# core.net
KiCad netlist of a schematic drawn in Altium Designer
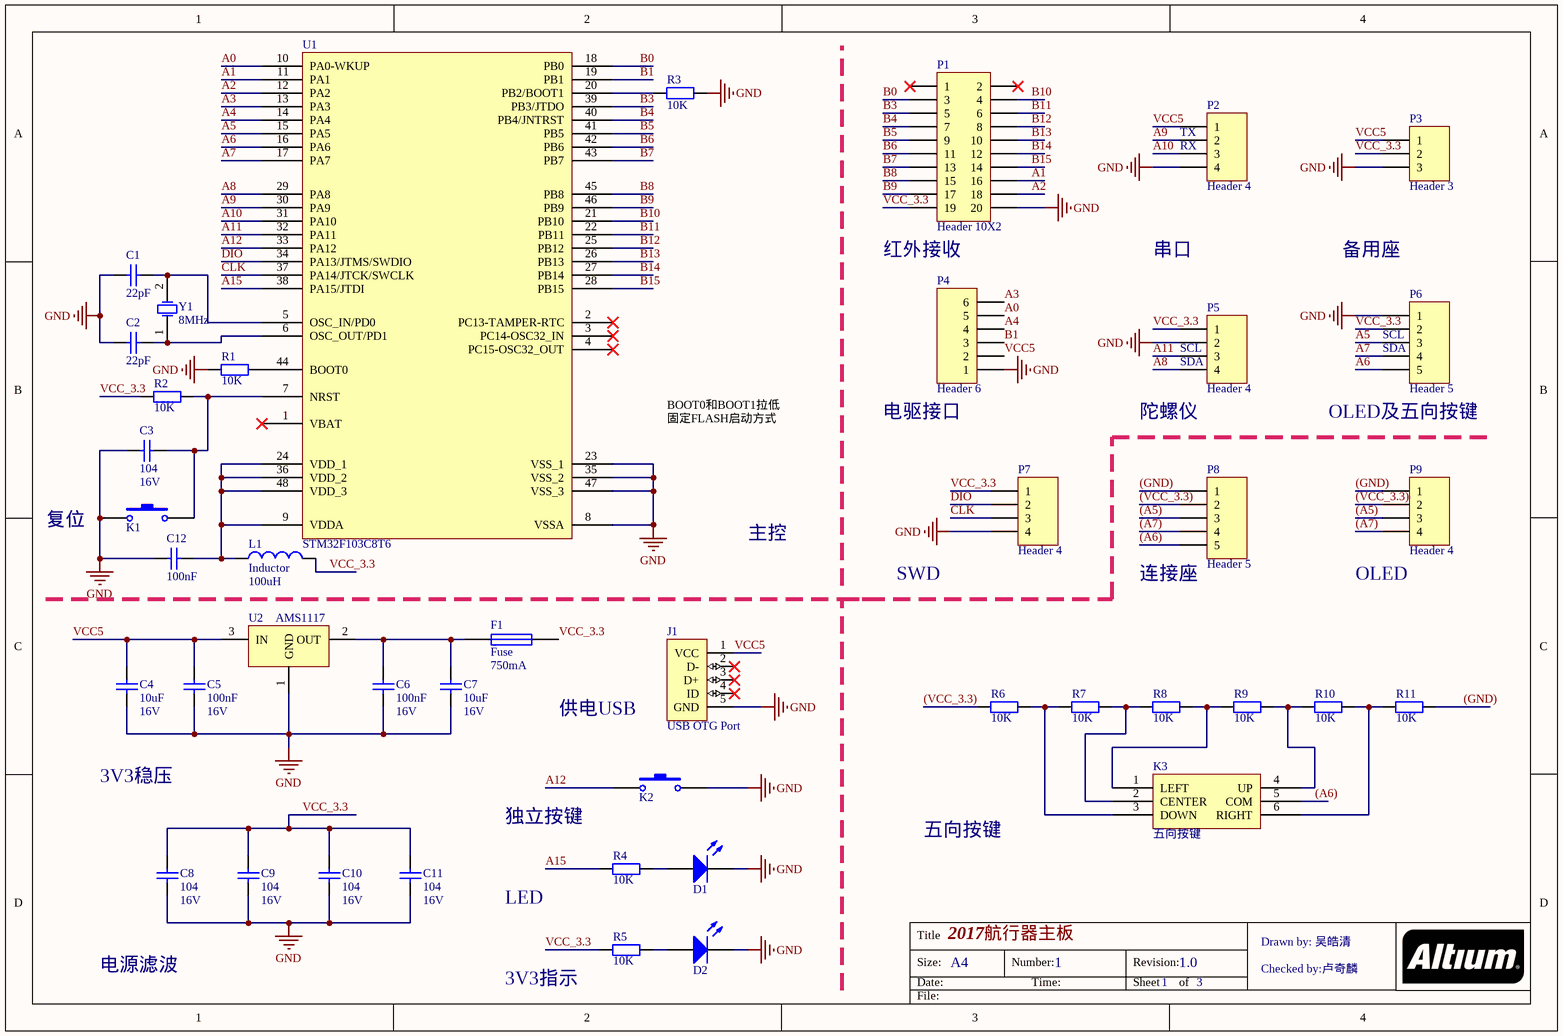
[diagram p0: core.SchDoc]

(export (version "E")
  (design (tool "Eeschema 10.0.6"))
  (components
    (comp (ref "C1")
      (value "22pF")
      (footprint "0805")
      (fields
        (field (name "Comment") "Cap")
        (field (name "原理图绘制者") "刘永钦")
        (field (name "原理图提供者") "刘永钦")
        (field (name "原理图审核人1") "徐鹏飞")
        (field (name "封装0805绘制者") "刘永钦")
        (field (name "封装0805提供者") "刘永钦")
        (field (name "封装0805审核人1") "徐鹏飞")
        (field (name "原理图审核人2") "朱觉文")
        (field (name "封装0805审核人2") "朱觉文")
        (field (name "封装0603绘制者") "刘永钦")
        (field (name "封装0603提供者") "刘永钦")
        (field (name "封装0603审核人1") "朱觉文")
        (field (name "封装0603审核人2") "徐鹏飞")
      )
      (libsource (lib "自动化研究所集成库20170403") (part "Cap"))
    )
    (comp (ref "C2")
      (value "22pF")
      (footprint "0805")
      (fields
        (field (name "Comment") "Cap")
        (field (name "原理图绘制者") "刘永钦")
        (field (name "原理图提供者") "刘永钦")
        (field (name "原理图审核人1") "徐鹏飞")
        (field (name "封装0805绘制者") "刘永钦")
        (field (name "封装0805提供者") "刘永钦")
        (field (name "封装0805审核人1") "徐鹏飞")
        (field (name "原理图审核人2") "朱觉文")
        (field (name "封装0805审核人2") "朱觉文")
        (field (name "封装0603绘制者") "刘永钦")
        (field (name "封装0603提供者") "刘永钦")
        (field (name "封装0603审核人1") "朱觉文")
        (field (name "封装0603审核人2") "徐鹏飞")
      )
      (libsource (lib "自动化研究所集成库20170403") (part "Cap"))
    )
    (comp (ref "C3")
      (value "104")
      (footprint "0805")
      (fields
        (field (name "PRESSURE VOLTAGE") "16V")
        (field (name "Comment") "Cap")
        (field (name "原理图绘制者") "刘永钦")
        (field (name "原理图提供者") "刘永钦")
        (field (name "原理图审核人1") "徐鹏飞")
        (field (name "封装0805绘制者") "刘永钦")
        (field (name "封装0805提供者") "刘永钦")
        (field (name "封装0805审核人1") "徐鹏飞")
        (field (name "原理图审核人2") "朱觉文")
        (field (name "封装0805审核人2") "朱觉文")
        (field (name "封装0603绘制者") "刘永钦")
        (field (name "封装0603提供者") "刘永钦")
        (field (name "封装0603审核人1") "朱觉文")
        (field (name "封装0603审核人2") "徐鹏飞")
      )
      (libsource (lib "自动化研究所集成库20170403") (part "Cap"))
    )
    (comp (ref "C4")
      (value "10uF")
      (footprint "0805")
      (fields
        (field (name "PRESSURE VOLTAGE") "16V")
        (field (name "Comment") "Cap")
        (field (name "原理图绘制者") "刘永钦")
        (field (name "原理图提供者") "刘永钦")
        (field (name "原理图审核人1") "徐鹏飞")
        (field (name "封装0805绘制者") "刘永钦")
        (field (name "封装0805提供者") "刘永钦")
        (field (name "封装0805审核人1") "徐鹏飞")
        (field (name "原理图审核人2") "朱觉文")
        (field (name "封装0805审核人2") "朱觉文")
        (field (name "封装0603绘制者") "刘永钦")
        (field (name "封装0603提供者") "刘永钦")
        (field (name "封装0603审核人1") "朱觉文")
        (field (name "封装0603审核人2") "徐鹏飞")
      )
      (libsource (lib "自动化研究所集成库20170403") (part "Cap"))
    )
    (comp (ref "C5")
      (value "100nF")
      (footprint "0805")
      (fields
        (field (name "PRESSURE VOLTAGE") "16V")
        (field (name "Comment") "Cap")
        (field (name "原理图绘制者") "刘永钦")
        (field (name "原理图提供者") "刘永钦")
        (field (name "原理图审核人1") "徐鹏飞")
        (field (name "封装0805绘制者") "刘永钦")
        (field (name "封装0805提供者") "刘永钦")
        (field (name "封装0805审核人1") "徐鹏飞")
        (field (name "原理图审核人2") "朱觉文")
        (field (name "封装0805审核人2") "朱觉文")
        (field (name "封装0603绘制者") "刘永钦")
        (field (name "封装0603提供者") "刘永钦")
        (field (name "封装0603审核人1") "朱觉文")
        (field (name "封装0603审核人2") "徐鹏飞")
      )
      (libsource (lib "自动化研究所集成库20170403") (part "Cap"))
    )
    (comp (ref "C6")
      (value "100nF")
      (footprint "0805")
      (fields
        (field (name "PRESSURE VOLTAGE") "16V")
        (field (name "Comment") "Cap")
        (field (name "原理图绘制者") "刘永钦")
        (field (name "原理图提供者") "刘永钦")
        (field (name "原理图审核人1") "徐鹏飞")
        (field (name "封装0805绘制者") "刘永钦")
        (field (name "封装0805提供者") "刘永钦")
        (field (name "封装0805审核人1") "徐鹏飞")
        (field (name "原理图审核人2") "朱觉文")
        (field (name "封装0805审核人2") "朱觉文")
        (field (name "封装0603绘制者") "刘永钦")
        (field (name "封装0603提供者") "刘永钦")
        (field (name "封装0603审核人1") "朱觉文")
        (field (name "封装0603审核人2") "徐鹏飞")
      )
      (libsource (lib "自动化研究所集成库20170403") (part "Cap"))
    )
    (comp (ref "C7")
      (value "10uF")
      (footprint "0805")
      (fields
        (field (name "PRESSURE VOLTAGE") "16V")
        (field (name "Comment") "Cap")
        (field (name "原理图绘制者") "刘永钦")
        (field (name "原理图提供者") "刘永钦")
        (field (name "原理图审核人1") "徐鹏飞")
        (field (name "封装0805绘制者") "刘永钦")
        (field (name "封装0805提供者") "刘永钦")
        (field (name "封装0805审核人1") "徐鹏飞")
        (field (name "原理图审核人2") "朱觉文")
        (field (name "封装0805审核人2") "朱觉文")
        (field (name "封装0603绘制者") "刘永钦")
        (field (name "封装0603提供者") "刘永钦")
        (field (name "封装0603审核人1") "朱觉文")
        (field (name "封装0603审核人2") "徐鹏飞")
      )
      (libsource (lib "自动化研究所集成库20170403") (part "Cap"))
    )
    (comp (ref "C8")
      (value "104")
      (footprint "0805")
      (fields
        (field (name "PRESSURE VOLTAGE") "16V")
        (field (name "Comment") "Cap")
        (field (name "原理图绘制者") "刘永钦")
        (field (name "原理图提供者") "刘永钦")
        (field (name "原理图审核人1") "徐鹏飞")
        (field (name "封装0805绘制者") "刘永钦")
        (field (name "封装0805提供者") "刘永钦")
        (field (name "封装0805审核人1") "徐鹏飞")
        (field (name "原理图审核人2") "朱觉文")
        (field (name "封装0805审核人2") "朱觉文")
        (field (name "封装0603绘制者") "刘永钦")
        (field (name "封装0603提供者") "刘永钦")
        (field (name "封装0603审核人1") "朱觉文")
        (field (name "封装0603审核人2") "徐鹏飞")
      )
      (libsource (lib "自动化研究所集成库20170403") (part "Cap"))
    )
    (comp (ref "C9")
      (value "104")
      (footprint "0805")
      (fields
        (field (name "PRESSURE VOLTAGE") "16V")
        (field (name "Comment") "Cap")
        (field (name "原理图绘制者") "刘永钦")
        (field (name "原理图提供者") "刘永钦")
        (field (name "原理图审核人1") "徐鹏飞")
        (field (name "封装0805绘制者") "刘永钦")
        (field (name "封装0805提供者") "刘永钦")
        (field (name "封装0805审核人1") "徐鹏飞")
        (field (name "原理图审核人2") "朱觉文")
        (field (name "封装0805审核人2") "朱觉文")
        (field (name "封装0603绘制者") "刘永钦")
        (field (name "封装0603提供者") "刘永钦")
        (field (name "封装0603审核人1") "朱觉文")
        (field (name "封装0603审核人2") "徐鹏飞")
      )
      (libsource (lib "自动化研究所集成库20170403") (part "Cap"))
    )
    (comp (ref "C10")
      (value "104")
      (footprint "0805")
      (fields
        (field (name "PRESSURE VOLTAGE") "16V")
        (field (name "Comment") "Cap")
        (field (name "原理图绘制者") "刘永钦")
        (field (name "原理图提供者") "刘永钦")
        (field (name "原理图审核人1") "徐鹏飞")
        (field (name "封装0805绘制者") "刘永钦")
        (field (name "封装0805提供者") "刘永钦")
        (field (name "封装0805审核人1") "徐鹏飞")
        (field (name "原理图审核人2") "朱觉文")
        (field (name "封装0805审核人2") "朱觉文")
        (field (name "封装0603绘制者") "刘永钦")
        (field (name "封装0603提供者") "刘永钦")
        (field (name "封装0603审核人1") "朱觉文")
        (field (name "封装0603审核人2") "徐鹏飞")
      )
      (libsource (lib "自动化研究所集成库20170403") (part "Cap"))
    )
    (comp (ref "C11")
      (value "104")
      (footprint "0805")
      (fields
        (field (name "PRESSURE VOLTAGE") "16V")
        (field (name "Comment") "Cap")
        (field (name "原理图绘制者") "刘永钦")
        (field (name "原理图提供者") "刘永钦")
        (field (name "原理图审核人1") "徐鹏飞")
        (field (name "封装0805绘制者") "刘永钦")
        (field (name "封装0805提供者") "刘永钦")
        (field (name "封装0805审核人1") "徐鹏飞")
        (field (name "原理图审核人2") "朱觉文")
        (field (name "封装0805审核人2") "朱觉文")
        (field (name "封装0603绘制者") "刘永钦")
        (field (name "封装0603提供者") "刘永钦")
        (field (name "封装0603审核人1") "朱觉文")
        (field (name "封装0603审核人2") "徐鹏飞")
      )
      (libsource (lib "自动化研究所集成库20170403") (part "Cap"))
    )
    (comp (ref "C12")
      (value "100nF")
      (footprint "0805")
      (fields
        (field (name "Comment") "Cap")
        (field (name "原理图绘制者") "刘永钦")
        (field (name "原理图提供者") "刘永钦")
        (field (name "原理图审核人1") "徐鹏飞")
        (field (name "封装0805绘制者") "刘永钦")
        (field (name "封装0805提供者") "刘永钦")
        (field (name "封装0805审核人1") "徐鹏飞")
        (field (name "原理图审核人2") "朱觉文")
        (field (name "封装0805审核人2") "朱觉文")
        (field (name "封装0603绘制者") "刘永钦")
        (field (name "封装0603提供者") "刘永钦")
        (field (name "封装0603审核人1") "朱觉文")
        (field (name "封装0603审核人2") "徐鹏飞")
      )
      (libsource (lib "自动化研究所集成库20170403") (part "Cap"))
    )
    (comp (ref "D1")
      (value "LED")
      (footprint "LED_0805")
      (fields
        (field (name "原理图绘制者") "刘永钦")
        (field (name "原理图提供者") "刘永钦")
        (field (name "原理图审核人1") "徐鹏飞")
        (field (name "封装1210LED绘制者") "刘永钦")
        (field (name "封装1210LED提供者") "刘永钦")
        (field (name "封装1210LED审核人1") "徐鹏飞")
        (field (name "封装LED_3MM绘制者") "刘永钦")
        (field (name "封装LED_3MM提供者") "刘永钦")
        (field (name "封装LED_0805绘制者") "刘永钦")
        (field (name "封装LED_0805提供者") "刘永钦")
        (field (name "封装LED_0805审核人1") "徐鹏飞")
        (field (name "原理图审核人2") "朱觉文")
        (field (name "封装1210LED审核人2") "朱觉文")
        (field (name "封装LED_0805审核人2") "朱觉文")
        (field (name "封装LED_3MM审核者2") "朱觉文")
        (field (name "封装LED0603绘制者") "刘永钦")
        (field (name "封装LED0603审核人2") "朱觉文")
        (field (name "封装LED0603提供者") "刘永钦")
        (field (name "封装LED0603审核人1") "徐鹏飞")
      )
      (libsource (lib "自动化研究所集成库20170403") (part "LED"))
    )
    (comp (ref "D2")
      (value "LED")
      (footprint "LED_0805")
      (fields
        (field (name "原理图绘制者") "刘永钦")
        (field (name "原理图提供者") "刘永钦")
        (field (name "原理图审核人1") "徐鹏飞")
        (field (name "封装1210LED绘制者") "刘永钦")
        (field (name "封装1210LED提供者") "刘永钦")
        (field (name "封装1210LED审核人1") "徐鹏飞")
        (field (name "封装LED_3MM绘制者") "刘永钦")
        (field (name "封装LED_3MM提供者") "刘永钦")
        (field (name "封装LED_0805绘制者") "刘永钦")
        (field (name "封装LED_0805提供者") "刘永钦")
        (field (name "封装LED_0805审核人1") "徐鹏飞")
        (field (name "原理图审核人2") "朱觉文")
        (field (name "封装1210LED审核人2") "朱觉文")
        (field (name "封装LED_0805审核人2") "朱觉文")
        (field (name "封装LED_3MM审核者2") "朱觉文")
        (field (name "封装LED0603绘制者") "刘永钦")
        (field (name "封装LED0603审核人2") "朱觉文")
        (field (name "封装LED0603提供者") "刘永钦")
        (field (name "封装LED0603审核人1") "徐鹏飞")
      )
      (libsource (lib "自动化研究所集成库20170403") (part "LED"))
    )
    (comp (ref "F1")
      (value "Fuse")
      (footprint "0805")
      (fields
        (field (name "I HOLD") "750mA")
        (field (name "封装1812审核人2") "朱觉文")
        (field (name "封装1812审核人1") "徐鹏飞")
        (field (name "封装1812提供者") "刘永钦")
        (field (name "封装1812绘制者") "刘永钦")
        (field (name "原理图审核人2") "朱觉文")
        (field (name "原理图审核人1") "徐鹏飞")
        (field (name "原理图提供者") "刘永钦")
        (field (name "原理图绘制者") "刘永钦")
      )
      (libsource (lib "自动化研究所集成库20170403") (part "Fuse"))
    )
    (comp (ref "J1")
      (value "USB OTG Port")
      (footprint "Micro USB母座贴片")
      (fields
        (field (name "原理图绘制者") "刘永钦")
        (field (name "原理图提供者") "刘永钦")
        (field (name "原理图审核人1") "徐鹏飞")
        (field (name "封装MICRO USB母座贴片绘制者") "刘永钦")
        (field (name "封装MICRO USB母座贴片提供者") "刘永钦")
        (field (name "封装MICRO USB母座贴片审核人1") "徐鹏飞")
        (field (name "原理图审核人2") "朱觉文")
        (field (name "封装MICRO USB母座贴片审核人2") "朱觉文")
      )
      (libsource (lib "自动化研究所集成库20170403") (part "USB OTG Port"))
    )
    (comp (ref "K1")
      (value "Key")
      (footprint "贴片按键3*6mm")
      (fields
        (field (name "原理图绘制者") "刘永钦")
        (field (name "原理图提供者") "刘永钦")
        (field (name "原理图审核人1") "徐鹏飞")
        (field (name "封装贴片按键3*6MM绘制者") "刘永钦")
        (field (name "封装贴片按键3*6MM提供者") "刘永钦")
        (field (name "封装贴片按键3*6MM审核人1") "徐鹏飞")
        (field (name "封装四脚按键6*6MM绘制者") "刘永钦")
        (field (name "封装四脚按键6*6MM提供者") "刘永钦")
        (field (name "封装四脚按键6*6MM审核人1") "徐鹏飞")
        (field (name "原理图审核人2") "朱觉文")
        (field (name "封装四脚按键6*6MM审核人2") "朱觉文")
        (field (name "封装贴片按键3*6MM审核人2") "朱觉文")
      )
      (libsource (lib "自动化研究所集成库20170403") (part "Key"))
    )
    (comp (ref "K2")
      (value "Key")
      (footprint "贴片按键3*6mm")
      (fields
        (field (name "原理图绘制者") "刘永钦")
        (field (name "原理图提供者") "刘永钦")
        (field (name "原理图审核人1") "徐鹏飞")
        (field (name "封装贴片按键3*6MM绘制者") "刘永钦")
        (field (name "封装贴片按键3*6MM提供者") "刘永钦")
        (field (name "封装贴片按键3*6MM审核人1") "徐鹏飞")
        (field (name "封装四脚按键6*6MM绘制者") "刘永钦")
        (field (name "封装四脚按键6*6MM提供者") "刘永钦")
        (field (name "封装四脚按键6*6MM审核人1") "徐鹏飞")
        (field (name "原理图审核人2") "朱觉文")
        (field (name "封装四脚按键6*6MM审核人2") "朱觉文")
        (field (name "封装贴片按键3*6MM审核人2") "朱觉文")
      )
      (libsource (lib "自动化研究所集成库20170403") (part "Key"))
    )
    (comp (ref "K3") (value "五向按键") (footprint "五向按键") (libsource (lib "自动化研究所集成库20170403") (part "五向按键")))
    (comp (ref "L1")
      (value "Inductor")
      (footprint "0805")
      (fields
        (field (name "ALTIUM_VALUE") "100uH")
        (field (name "原理图绘制者") "刘永钦")
        (field (name "原理图提供者") "刘永钦")
        (field (name "原理图审核人1") "徐鹏飞")
        (field (name "封装0805_INDUCTOR绘制者") "未知")
        (field (name "封装0805_INDUCTOR提供者") "刘永钦")
        (field (name "封装0805_INDUCTOR审核人1") "徐鹏飞")
        (field (name "原理图审核人2") "朱觉文")
        (field (name "封装0805_INDUCTOR审核人2") "朱觉文")
      )
      (libsource (lib "自动化研究所集成库20170403") (part "Inductor"))
    )
    (comp (ref "P1")
      (value "Header 10X2")
      (footprint "HDR2X10")
      (description "Header, 10-Pin, Dual row")
      (fields (field (name "PUBLISHER") "Altium Limited"))
      (libsource (lib "Miscellaneous Connectors") (part "Header 10X2"))
    )
    (comp (ref "P2")
      (value "Header 4")
      (footprint "HDR1X4")
      (description "Header, 4-Pin")
      (fields (field (name "PUBLISHER") "Altium Limited"))
      (libsource (lib "Miscellaneous Connectors") (part "Header 4"))
    )
    (comp (ref "P3")
      (value "Header 3")
      (footprint "HDR1X3")
      (description "Header, 3-Pin")
      (fields (field (name "PUBLISHER") "Altium Limited"))
      (libsource (lib "Miscellaneous Connectors") (part "Header 3"))
    )
    (comp (ref "P4")
      (value "Header 6")
      (footprint "HDR1X6")
      (description "Header, 6-Pin")
      (fields (field (name "PUBLISHER") "Altium Limited"))
      (libsource (lib "Miscellaneous Connectors") (part "Header 6"))
    )
    (comp (ref "P5")
      (value "Header 4")
      (footprint "HDR1X4")
      (description "Header, 4-Pin")
      (fields (field (name "PUBLISHER") "Altium Limited"))
      (libsource (lib "Miscellaneous Connectors") (part "Header 4"))
    )
    (comp (ref "P6")
      (value "Header 5")
      (footprint "HDR1X5")
      (description "Header, 5-Pin")
      (fields (field (name "PUBLISHER") "Altium Limited"))
      (libsource (lib "Miscellaneous Connectors") (part "Header 5"))
    )
    (comp (ref "P7")
      (value "Header 4")
      (footprint "HDR1X4")
      (description "Header, 4-Pin")
      (fields (field (name "PUBLISHER") "Altium Limited"))
      (libsource (lib "Miscellaneous Connectors") (part "Header 4"))
    )
    (comp (ref "P8")
      (value "Header 5")
      (footprint "HDR1X5")
      (description "Header, 5-Pin")
      (fields (field (name "PUBLISHER") "Altium Limited"))
      (libsource (lib "Miscellaneous Connectors") (part "Header 5"))
    )
    (comp (ref "P9")
      (value "Header 4")
      (footprint "HDR1X4")
      (description "Header, 4-Pin")
      (fields (field (name "PUBLISHER") "Altium Limited"))
      (libsource (lib "Miscellaneous Connectors") (part "Header 4"))
    )
    (comp (ref "R1")
      (value "10K")
      (footprint "0805")
      (fields
        (field (name "Comment") "Res")
        (field (name "原理图绘制者") "刘永钦")
        (field (name "原理图提供者") "刘永钦")
        (field (name "原理图审核人1") "徐鹏飞")
        (field (name "封装0805绘制者") "刘永钦")
        (field (name "封装0805提供者") "刘永钦")
        (field (name "封装0805审核人1") "徐鹏飞")
        (field (name "原理图审核人2") "朱觉文")
        (field (name "封装0805审核人2") "朱觉文")
        (field (name "封装0603提供者") "刘永钦")
        (field (name "封装0603审核人2") "朱觉文")
        (field (name "封装0603审核人1") "徐鹏飞")
        (field (name "封装2512-RESC6332X06N审核人2") "朱觉文")
        (field (name "封装2512-RESC6332X06N提供者") "刘永钦")
        (field (name "封装2512-RESC6332X06N审核人1") "徐鹏飞")
        (field (name "封装0603绘制者") "刘永钦")
        (field (name "封装2512-RESC6332X06N绘制者") "刘永钦")
      )
      (libsource (lib "自动化研究所集成库20170403") (part "Res"))
    )
    (comp (ref "R2")
      (value "10K")
      (footprint "0805")
      (fields
        (field (name "Comment") "Res")
        (field (name "原理图绘制者") "刘永钦")
        (field (name "原理图提供者") "刘永钦")
        (field (name "原理图审核人1") "徐鹏飞")
        (field (name "封装0805绘制者") "刘永钦")
        (field (name "封装0805提供者") "刘永钦")
        (field (name "封装0805审核人1") "徐鹏飞")
        (field (name "原理图审核人2") "朱觉文")
        (field (name "封装0805审核人2") "朱觉文")
        (field (name "封装0603提供者") "刘永钦")
        (field (name "封装0603审核人2") "朱觉文")
        (field (name "封装0603审核人1") "徐鹏飞")
        (field (name "封装2512-RESC6332X06N审核人2") "朱觉文")
        (field (name "封装2512-RESC6332X06N提供者") "刘永钦")
        (field (name "封装2512-RESC6332X06N审核人1") "徐鹏飞")
        (field (name "封装0603绘制者") "刘永钦")
        (field (name "封装2512-RESC6332X06N绘制者") "刘永钦")
      )
      (libsource (lib "自动化研究所集成库20170403") (part "Res"))
    )
    (comp (ref "R3")
      (value "10K")
      (footprint "0805")
      (fields
        (field (name "Comment") "Res")
        (field (name "原理图绘制者") "刘永钦")
        (field (name "原理图提供者") "刘永钦")
        (field (name "原理图审核人1") "徐鹏飞")
        (field (name "封装0805绘制者") "刘永钦")
        (field (name "封装0805提供者") "刘永钦")
        (field (name "封装0805审核人1") "徐鹏飞")
        (field (name "原理图审核人2") "朱觉文")
        (field (name "封装0805审核人2") "朱觉文")
        (field (name "封装0603提供者") "刘永钦")
        (field (name "封装0603审核人2") "朱觉文")
        (field (name "封装0603审核人1") "徐鹏飞")
        (field (name "封装2512-RESC6332X06N审核人2") "朱觉文")
        (field (name "封装2512-RESC6332X06N提供者") "刘永钦")
        (field (name "封装2512-RESC6332X06N审核人1") "徐鹏飞")
        (field (name "封装0603绘制者") "刘永钦")
        (field (name "封装2512-RESC6332X06N绘制者") "刘永钦")
      )
      (libsource (lib "自动化研究所集成库20170403") (part "Res"))
    )
    (comp (ref "R4")
      (value "10K")
      (footprint "0805")
      (fields
        (field (name "Comment") "Res")
        (field (name "原理图绘制者") "刘永钦")
        (field (name "原理图提供者") "刘永钦")
        (field (name "原理图审核人1") "徐鹏飞")
        (field (name "封装0805绘制者") "刘永钦")
        (field (name "封装0805提供者") "刘永钦")
        (field (name "封装0805审核人1") "徐鹏飞")
        (field (name "原理图审核人2") "朱觉文")
        (field (name "封装0805审核人2") "朱觉文")
        (field (name "封装0603提供者") "刘永钦")
        (field (name "封装0603审核人2") "朱觉文")
        (field (name "封装0603审核人1") "徐鹏飞")
        (field (name "封装2512-RESC6332X06N审核人2") "朱觉文")
        (field (name "封装2512-RESC6332X06N提供者") "刘永钦")
        (field (name "封装2512-RESC6332X06N审核人1") "徐鹏飞")
        (field (name "封装0603绘制者") "刘永钦")
        (field (name "封装2512-RESC6332X06N绘制者") "刘永钦")
      )
      (libsource (lib "自动化研究所集成库20170403") (part "Res"))
    )
    (comp (ref "R5")
      (value "10K")
      (footprint "0805")
      (fields
        (field (name "Comment") "Res")
        (field (name "原理图绘制者") "刘永钦")
        (field (name "原理图提供者") "刘永钦")
        (field (name "原理图审核人1") "徐鹏飞")
        (field (name "封装0805绘制者") "刘永钦")
        (field (name "封装0805提供者") "刘永钦")
        (field (name "封装0805审核人1") "徐鹏飞")
        (field (name "原理图审核人2") "朱觉文")
        (field (name "封装0805审核人2") "朱觉文")
        (field (name "封装0603提供者") "刘永钦")
        (field (name "封装0603审核人2") "朱觉文")
        (field (name "封装0603审核人1") "徐鹏飞")
        (field (name "封装2512-RESC6332X06N审核人2") "朱觉文")
        (field (name "封装2512-RESC6332X06N提供者") "刘永钦")
        (field (name "封装2512-RESC6332X06N审核人1") "徐鹏飞")
        (field (name "封装0603绘制者") "刘永钦")
        (field (name "封装2512-RESC6332X06N绘制者") "刘永钦")
      )
      (libsource (lib "自动化研究所集成库20170403") (part "Res"))
    )
    (comp (ref "R6")
      (value "10K")
      (footprint "0805")
      (fields
        (field (name "Comment") "Res")
        (field (name "原理图绘制者") "刘永钦")
        (field (name "原理图提供者") "刘永钦")
        (field (name "原理图审核人1") "徐鹏飞")
        (field (name "封装0805绘制者") "刘永钦")
        (field (name "封装0805提供者") "刘永钦")
        (field (name "封装0805审核人1") "徐鹏飞")
        (field (name "原理图审核人2") "朱觉文")
        (field (name "封装0805审核人2") "朱觉文")
        (field (name "封装0603提供者") "刘永钦")
        (field (name "封装0603审核人2") "朱觉文")
        (field (name "封装0603审核人1") "徐鹏飞")
        (field (name "封装2512-RESC6332X06N审核人2") "朱觉文")
        (field (name "封装2512-RESC6332X06N提供者") "刘永钦")
        (field (name "封装2512-RESC6332X06N审核人1") "徐鹏飞")
        (field (name "封装0603绘制者") "刘永钦")
        (field (name "封装2512-RESC6332X06N绘制者") "刘永钦")
      )
      (libsource (lib "自动化研究所集成库20170403") (part "Res"))
    )
    (comp (ref "R7")
      (value "10K")
      (footprint "0805")
      (fields
        (field (name "Comment") "Res")
        (field (name "原理图绘制者") "刘永钦")
        (field (name "原理图提供者") "刘永钦")
        (field (name "原理图审核人1") "徐鹏飞")
        (field (name "封装0805绘制者") "刘永钦")
        (field (name "封装0805提供者") "刘永钦")
        (field (name "封装0805审核人1") "徐鹏飞")
        (field (name "原理图审核人2") "朱觉文")
        (field (name "封装0805审核人2") "朱觉文")
        (field (name "封装0603提供者") "刘永钦")
        (field (name "封装0603审核人2") "朱觉文")
        (field (name "封装0603审核人1") "徐鹏飞")
        (field (name "封装2512-RESC6332X06N审核人2") "朱觉文")
        (field (name "封装2512-RESC6332X06N提供者") "刘永钦")
        (field (name "封装2512-RESC6332X06N审核人1") "徐鹏飞")
        (field (name "封装0603绘制者") "刘永钦")
        (field (name "封装2512-RESC6332X06N绘制者") "刘永钦")
      )
      (libsource (lib "自动化研究所集成库20170403") (part "Res"))
    )
    (comp (ref "R8")
      (value "10K")
      (footprint "0805")
      (fields
        (field (name "Comment") "Res")
        (field (name "原理图绘制者") "刘永钦")
        (field (name "原理图提供者") "刘永钦")
        (field (name "原理图审核人1") "徐鹏飞")
        (field (name "封装0805绘制者") "刘永钦")
        (field (name "封装0805提供者") "刘永钦")
        (field (name "封装0805审核人1") "徐鹏飞")
        (field (name "原理图审核人2") "朱觉文")
        (field (name "封装0805审核人2") "朱觉文")
        (field (name "封装0603提供者") "刘永钦")
        (field (name "封装0603审核人2") "朱觉文")
        (field (name "封装0603审核人1") "徐鹏飞")
        (field (name "封装2512-RESC6332X06N审核人2") "朱觉文")
        (field (name "封装2512-RESC6332X06N提供者") "刘永钦")
        (field (name "封装2512-RESC6332X06N审核人1") "徐鹏飞")
        (field (name "封装0603绘制者") "刘永钦")
        (field (name "封装2512-RESC6332X06N绘制者") "刘永钦")
      )
      (libsource (lib "自动化研究所集成库20170403") (part "Res"))
    )
    (comp (ref "R9")
      (value "10K")
      (footprint "0805")
      (fields
        (field (name "Comment") "Res")
        (field (name "原理图绘制者") "刘永钦")
        (field (name "原理图提供者") "刘永钦")
        (field (name "原理图审核人1") "徐鹏飞")
        (field (name "封装0805绘制者") "刘永钦")
        (field (name "封装0805提供者") "刘永钦")
        (field (name "封装0805审核人1") "徐鹏飞")
        (field (name "原理图审核人2") "朱觉文")
        (field (name "封装0805审核人2") "朱觉文")
        (field (name "封装0603提供者") "刘永钦")
        (field (name "封装0603审核人2") "朱觉文")
        (field (name "封装0603审核人1") "徐鹏飞")
        (field (name "封装2512-RESC6332X06N审核人2") "朱觉文")
        (field (name "封装2512-RESC6332X06N提供者") "刘永钦")
        (field (name "封装2512-RESC6332X06N审核人1") "徐鹏飞")
        (field (name "封装0603绘制者") "刘永钦")
        (field (name "封装2512-RESC6332X06N绘制者") "刘永钦")
      )
      (libsource (lib "自动化研究所集成库20170403") (part "Res"))
    )
    (comp (ref "R10")
      (value "10K")
      (footprint "0805")
      (fields
        (field (name "Comment") "Res")
        (field (name "原理图绘制者") "刘永钦")
        (field (name "原理图提供者") "刘永钦")
        (field (name "原理图审核人1") "徐鹏飞")
        (field (name "封装0805绘制者") "刘永钦")
        (field (name "封装0805提供者") "刘永钦")
        (field (name "封装0805审核人1") "徐鹏飞")
        (field (name "原理图审核人2") "朱觉文")
        (field (name "封装0805审核人2") "朱觉文")
        (field (name "封装0603提供者") "刘永钦")
        (field (name "封装0603审核人2") "朱觉文")
        (field (name "封装0603审核人1") "徐鹏飞")
        (field (name "封装2512-RESC6332X06N审核人2") "朱觉文")
        (field (name "封装2512-RESC6332X06N提供者") "刘永钦")
        (field (name "封装2512-RESC6332X06N审核人1") "徐鹏飞")
        (field (name "封装0603绘制者") "刘永钦")
        (field (name "封装2512-RESC6332X06N绘制者") "刘永钦")
      )
      (libsource (lib "自动化研究所集成库20170403") (part "Res"))
    )
    (comp (ref "R11")
      (value "10K")
      (footprint "0805")
      (fields
        (field (name "Comment") "Res")
        (field (name "原理图绘制者") "刘永钦")
        (field (name "原理图提供者") "刘永钦")
        (field (name "原理图审核人1") "徐鹏飞")
        (field (name "封装0805绘制者") "刘永钦")
        (field (name "封装0805提供者") "刘永钦")
        (field (name "封装0805审核人1") "徐鹏飞")
        (field (name "原理图审核人2") "朱觉文")
        (field (name "封装0805审核人2") "朱觉文")
        (field (name "封装0603提供者") "刘永钦")
        (field (name "封装0603审核人2") "朱觉文")
        (field (name "封装0603审核人1") "徐鹏飞")
        (field (name "封装2512-RESC6332X06N审核人2") "朱觉文")
        (field (name "封装2512-RESC6332X06N提供者") "刘永钦")
        (field (name "封装2512-RESC6332X06N审核人1") "徐鹏飞")
        (field (name "封装0603绘制者") "刘永钦")
        (field (name "封装2512-RESC6332X06N绘制者") "刘永钦")
      )
      (libsource (lib "自动化研究所集成库20170403") (part "Res"))
    )
    (comp (ref "U1")
      (value "STM32F103C8T6")
      (footprint "STM32F103C8T6")
      (libsource (lib "自动化研究所集成库20170403") (part "STM32F103C8T6"))
    )
    (comp (ref "U2")
      (value "AMS1117")
      (footprint "AMS1117")
      (fields
        (field (name "原理图绘制者") "刘永钦")
        (field (name "原理图提供者") "刘永钦")
        (field (name "原理图审核人1") "徐鹏飞")
        (field (name "封装AMS1117绘制者") "刘永钦")
        (field (name "封装AMS1117提供者") "刘永钦")
        (field (name "封装AMS1117审核人1") "徐鹏飞")
        (field (name "原理图审核人2") "朱觉文")
        (field (name "封装AMS1117审核人2") "朱觉文")
      )
      (libsource (lib "自动化研究所集成库20170403") (part "AMS1117"))
    )
    (comp (ref "Y1")
      (value "8MHz")
      (footprint "晶振49S型")
      (fields
        (field (name "Comment") "晶振")
        (field (name "原理图绘制者") "刘永钦")
        (field (name "原理图提供者") "刘永钦")
        (field (name "原理图审核人1") "徐鹏飞")
        (field (name "封装晶振49S型绘制者") "刘永钦")
        (field (name "封装晶振49S型审核人1") "徐鹏飞")
        (field (name "封装晶振49S型提供者") "刘永钦")
        (field (name "原理图审核人2") "朱觉文")
        (field (name "封装晶振49S型审核人2") "朱觉文")
        (field (name "封装晶振49SMD绘制者") "刘永钦")
        (field (name "封装晶振49SMD提供者") "刘永钦")
        (field (name "封装晶振49SMD审核人2") "朱觉文")
        (field (name "封装晶振49SMD审核人1") "徐鹏飞")
      )
      (libsource (lib "自动化研究所集成库20170403") (part "晶振"))
    )
  )
  (nets
    (net (code "1") (name "/(A5)") (class "Default")
      (node (ref "P8") (pin "3") (pinfunction "3_3") (pintype "passive"))
      (node (ref "P9") (pin "3") (pinfunction "3_3") (pintype "passive"))
    )
    (net (code "2") (name "/(A6)") (class "Default")
      (node (ref "K3") (pin "5") (pinfunction "COM_5") (pintype "passive"))
      (node (ref "P8") (pin "5") (pinfunction "5_5") (pintype "passive"))
    )
    (net (code "3") (name "/(A7)") (class "Default")
      (node (ref "P8") (pin "4") (pinfunction "4_4") (pintype "passive"))
      (node (ref "P9") (pin "4") (pinfunction "4_4") (pintype "passive"))
    )
    (net (code "4") (name "/(GND)") (class "Default")
      (node (ref "P8") (pin "1") (pinfunction "1_1") (pintype "passive"))
      (node (ref "P9") (pin "1") (pinfunction "1_1") (pintype "passive"))
      (node (ref "R11") (pin "2") (pinfunction "2_2") (pintype "passive"))
    )
    (net (code "5") (name "/(VCC_3.3)") (class "Default")
      (node (ref "P8") (pin "2") (pinfunction "2_2") (pintype "passive"))
      (node (ref "P9") (pin "2") (pinfunction "2_2") (pintype "passive"))
      (node (ref "R6") (pin "1") (pinfunction "1_1") (pintype "passive"))
    )
    (net (code "6") (name "/A0") (class "Default")
      (node (ref "P4") (pin "5") (pinfunction "5_5") (pintype "passive"))
      (node (ref "U1") (pin "10") (pinfunction "PA0-WKUP_10") (pintype "passive"))
    )
    (net (code "7") (name "/A1") (class "Default")
      (node (ref "P1") (pin "16") (pinfunction "16_16") (pintype "passive"))
      (node (ref "U1") (pin "11") (pinfunction "PA1_11") (pintype "passive"))
    )
    (net (code "8") (name "/A2") (class "Default")
      (node (ref "P1") (pin "18") (pinfunction "18_18") (pintype "passive"))
      (node (ref "U1") (pin "12") (pinfunction "PA2_12") (pintype "passive"))
    )
    (net (code "9") (name "/A3") (class "Default")
      (node (ref "P4") (pin "6") (pinfunction "6_6") (pintype "passive"))
      (node (ref "U1") (pin "13") (pinfunction "PA3_13") (pintype "passive"))
    )
    (net (code "10") (name "/A4") (class "Default")
      (node (ref "P4") (pin "4") (pinfunction "4_4") (pintype "passive"))
      (node (ref "U1") (pin "14") (pinfunction "PA4_14") (pintype "passive"))
    )
    (net (code "11") (name "/A5") (class "Default")
      (node (ref "P6") (pin "3") (pinfunction "3_3") (pintype "passive"))
      (node (ref "U1") (pin "15") (pinfunction "PA5_15") (pintype "passive"))
    )
    (net (code "12") (name "/A6") (class "Default")
      (node (ref "P6") (pin "5") (pinfunction "5_5") (pintype "passive"))
      (node (ref "U1") (pin "16") (pinfunction "PA6_16") (pintype "passive"))
    )
    (net (code "13") (name "/A7") (class "Default")
      (node (ref "P6") (pin "4") (pinfunction "4_4") (pintype "passive"))
      (node (ref "U1") (pin "17") (pinfunction "PA7_17") (pintype "passive"))
    )
    (net (code "14") (name "/A8") (class "Default")
      (node (ref "P5") (pin "4") (pinfunction "4_4") (pintype "passive"))
      (node (ref "U1") (pin "29") (pinfunction "PA8_29") (pintype "passive"))
    )
    (net (code "15") (name "/A9") (class "Default")
      (node (ref "P2") (pin "2") (pinfunction "2_2") (pintype "passive"))
      (node (ref "U1") (pin "30") (pinfunction "PA9_30") (pintype "passive"))
    )
    (net (code "16") (name "/A10") (class "Default")
      (node (ref "P2") (pin "3") (pinfunction "3_3") (pintype "passive"))
      (node (ref "U1") (pin "31") (pinfunction "PA10_31") (pintype "passive"))
    )
    (net (code "17") (name "/A11") (class "Default")
      (node (ref "P5") (pin "3") (pinfunction "3_3") (pintype "passive"))
      (node (ref "U1") (pin "32") (pinfunction "PA11_32") (pintype "passive"))
    )
    (net (code "18") (name "/A12") (class "Default")
      (node (ref "K2") (pin "1") (pinfunction "1_1") (pintype "passive"))
      (node (ref "U1") (pin "33") (pinfunction "PA12_33") (pintype "passive"))
    )
    (net (code "19") (name "/A15") (class "Default")
      (node (ref "R4") (pin "1") (pinfunction "1_1") (pintype "passive"))
      (node (ref "U1") (pin "38") (pinfunction "PA15/JTDI_38") (pintype "passive"))
    )
    (net (code "20") (name "/B0") (class "Default")
      (node (ref "P1") (pin "3") (pinfunction "3_3") (pintype "passive"))
      (node (ref "U1") (pin "18") (pinfunction "PB0_18") (pintype "passive"))
    )
    (net (code "21") (name "/B1") (class "Default")
      (node (ref "P4") (pin "3") (pinfunction "3_3") (pintype "passive"))
      (node (ref "U1") (pin "19") (pinfunction "PB1_19") (pintype "passive"))
    )
    (net (code "22") (name "/B3") (class "Default")
      (node (ref "P1") (pin "5") (pinfunction "5_5") (pintype "passive"))
      (node (ref "U1") (pin "39") (pinfunction "PB3/JTDO_39") (pintype "passive"))
    )
    (net (code "23") (name "/B4") (class "Default")
      (node (ref "P1") (pin "7") (pinfunction "7_7") (pintype "passive"))
      (node (ref "U1") (pin "40") (pinfunction "PB4/JNTRST_40") (pintype "passive"))
    )
    (net (code "24") (name "/B5") (class "Default")
      (node (ref "P1") (pin "9") (pinfunction "9_9") (pintype "passive"))
      (node (ref "U1") (pin "41") (pinfunction "PB5_41") (pintype "passive"))
    )
    (net (code "25") (name "/B6") (class "Default")
      (node (ref "P1") (pin "11") (pinfunction "11_11") (pintype "passive"))
      (node (ref "U1") (pin "42") (pinfunction "PB6_42") (pintype "passive"))
    )
    (net (code "26") (name "/B7") (class "Default")
      (node (ref "P1") (pin "13") (pinfunction "13_13") (pintype "passive"))
      (node (ref "U1") (pin "43") (pinfunction "PB7_43") (pintype "passive"))
    )
    (net (code "27") (name "/B8") (class "Default")
      (node (ref "P1") (pin "15") (pinfunction "15_15") (pintype "passive"))
      (node (ref "U1") (pin "45") (pinfunction "PB8_45") (pintype "passive"))
    )
    (net (code "28") (name "/B9") (class "Default")
      (node (ref "P1") (pin "17") (pinfunction "17_17") (pintype "passive"))
      (node (ref "U1") (pin "46") (pinfunction "PB9_46") (pintype "passive"))
    )
    (net (code "29") (name "/B10") (class "Default")
      (node (ref "P1") (pin "4") (pinfunction "4_4") (pintype "passive"))
      (node (ref "U1") (pin "21") (pinfunction "PB10_21") (pintype "passive"))
    )
    (net (code "30") (name "/B11") (class "Default")
      (node (ref "P1") (pin "6") (pinfunction "6_6") (pintype "passive"))
      (node (ref "U1") (pin "22") (pinfunction "PB11_22") (pintype "passive"))
    )
    (net (code "31") (name "/B12") (class "Default")
      (node (ref "P1") (pin "8") (pinfunction "8_8") (pintype "passive"))
      (node (ref "U1") (pin "25") (pinfunction "PB12_25") (pintype "passive"))
    )
    (net (code "32") (name "/B13") (class "Default")
      (node (ref "P1") (pin "10") (pinfunction "10_10") (pintype "passive"))
      (node (ref "U1") (pin "26") (pinfunction "PB13_26") (pintype "passive"))
    )
    (net (code "33") (name "/B14") (class "Default")
      (node (ref "P1") (pin "12") (pinfunction "12_12") (pintype "passive"))
      (node (ref "U1") (pin "27") (pinfunction "PB14_27") (pintype "passive"))
    )
    (net (code "34") (name "/B15") (class "Default")
      (node (ref "P1") (pin "14") (pinfunction "14_14") (pintype "passive"))
      (node (ref "U1") (pin "28") (pinfunction "PB15_28") (pintype "passive"))
    )
    (net (code "35") (name "/CLK") (class "Default")
      (node (ref "P7") (pin "3") (pinfunction "3_3") (pintype "passive"))
      (node (ref "U1") (pin "37") (pinfunction "PA14/JTCK/SWCLK_37") (pintype "passive"))
    )
    (net (code "36") (name "/DIO") (class "Default")
      (node (ref "P7") (pin "2") (pinfunction "2_2") (pintype "passive"))
      (node (ref "U1") (pin "34") (pinfunction "PA13/JTMS/SWDIO_34") (pintype "passive"))
    )
    (net (code "37") (name "/VCC5") (class "Default")
      (node (ref "C4") (pin "2") (pinfunction "2_2") (pintype "passive"))
      (node (ref "C5") (pin "2") (pinfunction "2_2") (pintype "passive"))
      (node (ref "J1") (pin "1") (pinfunction "VCC_1") (pintype "power_in"))
      (node (ref "P2") (pin "1") (pinfunction "1_1") (pintype "passive"))
      (node (ref "P3") (pin "1") (pinfunction "1_1") (pintype "passive"))
      (node (ref "P4") (pin "2") (pinfunction "2_2") (pintype "passive"))
      (node (ref "U2") (pin "3") (pinfunction "IN_3") (pintype "power_in"))
    )
    (net (code "38") (name "/VCC_3.3") (class "Default")
      (node (ref "C10") (pin "2") (pinfunction "2_2") (pintype "passive"))
      (node (ref "C11") (pin "2") (pinfunction "2_2") (pintype "passive"))
      (node (ref "C8") (pin "2") (pinfunction "2_2") (pintype "passive"))
      (node (ref "C9") (pin "2") (pinfunction "2_2") (pintype "passive"))
      (node (ref "F1") (pin "2") (pinfunction "2_2") (pintype "passive"))
      (node (ref "L1") (pin "2") (pinfunction "2_2") (pintype "passive"))
      (node (ref "P1") (pin "19") (pinfunction "19_19") (pintype "passive"))
      (node (ref "P3") (pin "2") (pinfunction "2_2") (pintype "passive"))
      (node (ref "P5") (pin "1") (pinfunction "1_1") (pintype "passive"))
      (node (ref "P6") (pin "2") (pinfunction "2_2") (pintype "passive"))
      (node (ref "P7") (pin "1") (pinfunction "1_1") (pintype "passive"))
      (node (ref "R2") (pin "1") (pinfunction "1_1") (pintype "passive"))
      (node (ref "R5") (pin "1") (pinfunction "1_1") (pintype "passive"))
    )
    (net (code "39") (name "GND") (class "Default")
      (node (ref "C1") (pin "1") (pinfunction "1_1") (pintype "passive"))
      (node (ref "C10") (pin "1") (pinfunction "1_1") (pintype "passive"))
      (node (ref "C11") (pin "1") (pinfunction "1_1") (pintype "passive"))
      (node (ref "C12") (pin "1") (pinfunction "1_1") (pintype "passive"))
      (node (ref "C2") (pin "1") (pinfunction "1_1") (pintype "passive"))
      (node (ref "C3") (pin "1") (pinfunction "1_1") (pintype "passive"))
      (node (ref "C4") (pin "1") (pinfunction "1_1") (pintype "passive"))
      (node (ref "C5") (pin "1") (pinfunction "1_1") (pintype "passive"))
      (node (ref "C6") (pin "1") (pinfunction "1_1") (pintype "passive"))
      (node (ref "C7") (pin "1") (pinfunction "1_1") (pintype "passive"))
      (node (ref "C8") (pin "1") (pinfunction "1_1") (pintype "passive"))
      (node (ref "C9") (pin "1") (pinfunction "1_1") (pintype "passive"))
      (node (ref "D1") (pin "2") (pinfunction "K_2") (pintype "passive"))
      (node (ref "D2") (pin "2") (pinfunction "K_2") (pintype "passive"))
      (node (ref "J1") (pin "5") (pinfunction "GND_5") (pintype "power_in"))
      (node (ref "K1") (pin "1") (pinfunction "1_1") (pintype "passive"))
      (node (ref "K2") (pin "2") (pinfunction "2_2") (pintype "passive"))
      (node (ref "P1") (pin "20") (pinfunction "20_20") (pintype "passive"))
      (node (ref "P2") (pin "4") (pinfunction "4_4") (pintype "passive"))
      (node (ref "P3") (pin "3") (pinfunction "3_3") (pintype "passive"))
      (node (ref "P4") (pin "1") (pinfunction "1_1") (pintype "passive"))
      (node (ref "P5") (pin "2") (pinfunction "2_2") (pintype "passive"))
      (node (ref "P6") (pin "1") (pinfunction "1_1") (pintype "passive"))
      (node (ref "P7") (pin "4") (pinfunction "4_4") (pintype "passive"))
      (node (ref "R1") (pin "1") (pinfunction "1_1") (pintype "passive"))
      (node (ref "R3") (pin "2") (pinfunction "2_2") (pintype "passive"))
      (node (ref "U1") (pin "23") (pinfunction "VSS_1_23") (pintype "passive"))
      (node (ref "U1") (pin "35") (pinfunction "VSS_2_35") (pintype "passive"))
      (node (ref "U1") (pin "47") (pinfunction "VSS_3_47") (pintype "passive"))
      (node (ref "U1") (pin "8") (pinfunction "VSSA_8") (pintype "passive"))
      (node (ref "U2") (pin "1") (pinfunction "GND_1") (pintype "power_in"))
    )
    (net (code "40") (name "Net-(D1-A)") (class "Default")
      (node (ref "D1") (pin "1") (pinfunction "A_1") (pintype "passive"))
      (node (ref "R4") (pin "2") (pinfunction "2_2") (pintype "passive"))
    )
    (net (code "41") (name "Net-(D2-A)") (class "Default")
      (node (ref "D2") (pin "1") (pinfunction "A_1") (pintype "passive"))
      (node (ref "R5") (pin "2") (pinfunction "2_2") (pintype "passive"))
    )
    (net (code "42") (name "Net-(K3-CENTER)") (class "Default")
      (node (ref "K3") (pin "2") (pinfunction "CENTER_2") (pintype "passive"))
      (node (ref "R7") (pin "2") (pinfunction "2_2") (pintype "passive"))
      (node (ref "R8") (pin "1") (pinfunction "1_1") (pintype "passive"))
    )
    (net (code "43") (name "Net-(K3-DOWN)") (class "Default")
      (node (ref "K3") (pin "3") (pinfunction "DOWN_3") (pintype "passive"))
      (node (ref "R6") (pin "2") (pinfunction "2_2") (pintype "passive"))
      (node (ref "R7") (pin "1") (pinfunction "1_1") (pintype "passive"))
    )
    (net (code "44") (name "Net-(K3-LEFT)") (class "Default")
      (node (ref "K3") (pin "1") (pinfunction "LEFT_1") (pintype "passive"))
      (node (ref "R8") (pin "2") (pinfunction "2_2") (pintype "passive"))
      (node (ref "R9") (pin "1") (pinfunction "1_1") (pintype "passive"))
    )
    (net (code "45") (name "Net-(K3-RIGHT)") (class "Default")
      (node (ref "K3") (pin "6") (pinfunction "RIGHT_6") (pintype "passive"))
      (node (ref "R10") (pin "2") (pinfunction "2_2") (pintype "passive"))
      (node (ref "R11") (pin "1") (pinfunction "1_1") (pintype "passive"))
    )
    (net (code "46") (name "Net-(K3-UP)") (class "Default")
      (node (ref "K3") (pin "4") (pinfunction "UP_4") (pintype "passive"))
      (node (ref "R10") (pin "1") (pinfunction "1_1") (pintype "passive"))
      (node (ref "R9") (pin "2") (pinfunction "2_2") (pintype "passive"))
    )
    (net (code "47") (name "Net-(U1-BOOT0)") (class "Default")
      (node (ref "R1") (pin "2") (pinfunction "2_2") (pintype "passive"))
      (node (ref "U1") (pin "44") (pinfunction "BOOT0_44") (pintype "passive"))
    )
    (net (code "48") (name "Net-(U1-NRST)") (class "Default")
      (node (ref "C3") (pin "2") (pinfunction "2_2") (pintype "passive"))
      (node (ref "K1") (pin "2") (pinfunction "2_2") (pintype "passive"))
      (node (ref "R2") (pin "2") (pinfunction "2_2") (pintype "passive"))
      (node (ref "U1") (pin "7") (pinfunction "NRST_7") (pintype "passive"))
    )
    (net (code "49") (name "Net-(U1-OSC_IN{slash}PD0)") (class "Default")
      (node (ref "C1") (pin "2") (pinfunction "2_2") (pintype "passive"))
      (node (ref "U1") (pin "5") (pinfunction "OSC_IN/PD0_5") (pintype "passive"))
      (node (ref "Y1") (pin "2") (pinfunction "OSC2_2") (pintype "passive"))
    )
    (net (code "50") (name "Net-(U1-OSC_OUT{slash}PD1)") (class "Default")
      (node (ref "C2") (pin "2") (pinfunction "2_2") (pintype "passive"))
      (node (ref "U1") (pin "6") (pinfunction "OSC_OUT/PD1_6") (pintype "passive"))
      (node (ref "Y1") (pin "1") (pinfunction "OSC1_1") (pintype "passive"))
    )
    (net (code "51") (name "Net-(U1-PB2{slash}BOOT1)") (class "Default")
      (node (ref "R3") (pin "1") (pinfunction "1_1") (pintype "passive"))
      (node (ref "U1") (pin "20") (pinfunction "PB2/BOOT1_20") (pintype "passive"))
    )
    (net (code "52") (name "Net-(U1-VDDA)") (class "Default")
      (node (ref "C12") (pin "2") (pinfunction "2_2") (pintype "passive"))
      (node (ref "L1") (pin "1") (pinfunction "1_1") (pintype "passive"))
      (node (ref "U1") (pin "24") (pinfunction "VDD_1_24") (pintype "passive"))
      (node (ref "U1") (pin "36") (pinfunction "VDD_2_36") (pintype "passive"))
      (node (ref "U1") (pin "48") (pinfunction "VDD_3_48") (pintype "passive"))
      (node (ref "U1") (pin "9") (pinfunction "VDDA_9") (pintype "passive"))
    )
    (net (code "53") (name "Net-(U2-OUT)") (class "Default")
      (node (ref "C6") (pin "2") (pinfunction "2_2") (pintype "passive"))
      (node (ref "C7") (pin "2") (pinfunction "2_2") (pintype "passive"))
      (node (ref "F1") (pin "1") (pinfunction "1_1") (pintype "passive"))
      (node (ref "U2") (pin "2") (pinfunction "OUT_2") (pintype "power_in"))
    )
    (net (code "54") (name "unconnected-(J1-D+-Pad3)") (class "Default")
      (node (ref "J1") (pin "3") (pinfunction "D+_3") (pintype "bidirectional+no_connect"))
    )
    (net (code "55") (name "unconnected-(J1-D--Pad2)") (class "Default")
      (node (ref "J1") (pin "2") (pinfunction "D-_2") (pintype "bidirectional+no_connect"))
    )
    (net (code "56") (name "unconnected-(J1-ID-Pad4)") (class "Default")
      (node (ref "J1") (pin "4") (pinfunction "ID_4") (pintype "bidirectional+no_connect"))
    )
    (net (code "57") (name "unconnected-(P1-Pad1)") (class "Default")
      (node (ref "P1") (pin "1") (pinfunction "1_1") (pintype "passive+no_connect"))
    )
    (net (code "58") (name "unconnected-(P1-Pad2)") (class "Default")
      (node (ref "P1") (pin "2") (pinfunction "2_2") (pintype "passive+no_connect"))
    )
    (net (code "59") (name "unconnected-(U1-PC13-TAMPER-RTC-Pad2)") (class "Default")
      (node (ref "U1") (pin "2") (pinfunction "PC13-TAMPER-RTC_2") (pintype "passive+no_connect"))
    )
    (net (code "60") (name "unconnected-(U1-PC14-OSC32_IN-Pad3)") (class "Default")
      (node (ref "U1") (pin "3") (pinfunction "PC14-OSC32_IN_3") (pintype "passive+no_connect"))
    )
    (net (code "61") (name "unconnected-(U1-PC15-OSC32_OUT-Pad4)") (class "Default")
      (node (ref "U1") (pin "4") (pinfunction "PC15-OSC32_OUT_4") (pintype "passive+no_connect"))
    )
    (net (code "62") (name "unconnected-(U1-VBAT-Pad1)") (class "Default")
      (node (ref "U1") (pin "1") (pinfunction "VBAT_1") (pintype "passive+no_connect"))
    )
  )
)
